# Power_Supply.net
KiCad netlist of a schematic drawn in Altium Designer
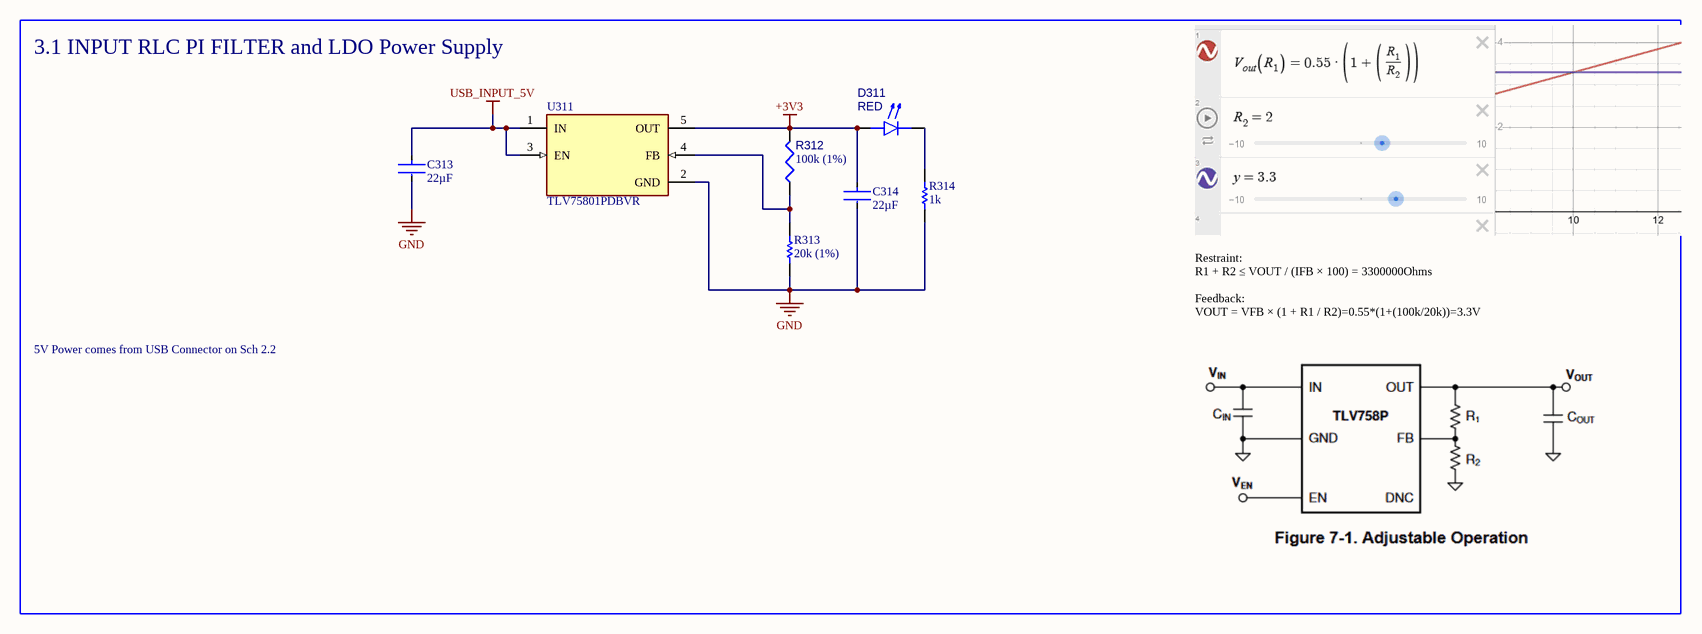
[diagram p0: Power Supply.SchDoc]

(export (version "E")
  (design (tool "Eeschema 10.0.6"))
  (components
    (comp (ref "C313")
      (value "22µF")
      (footprint "FP-GRM21B-0_2-e0_2_0_7-MFG")
      (fields (field (name "Comment") "GRM21BZ71A226ME15L"))
      (libsource (lib "University of British Columbia") (part "b4654b650e69147ec39a6b967a45e02"))
    )
    (comp (ref "C314")
      (value "22µF")
      (footprint "FP-GRM21B-0_2-e0_2_0_7-MFG")
      (fields (field (name "Comment") "GRM21BZ71A226ME15L"))
      (libsource (lib "University of British Columbia") (part "b4654b650e69147ec39a6b967a45e02"))
    )
    (comp (ref "D311")
      (value "RED")
      (footprint "WL-SMCW_0603_150060xx75000")
      (description "Single Color LED, Red, Water Clear, 1.1mm")
      (libsource (lib "University of British Columbia") (part "DIODE-LED-2"))
    )
    (comp (ref "R312")
      (value "100k (1%)")
      (footprint "RESC1608X55X25ML10T15")
      (description "Chip Resistor, 100 KOhm, +/- 1%, 0.1 W, -55 to 155 degC, 0603 (1608 Metric)")
      (fields (field (name "TOLERANCE") "1%") (field (name "POWER") "100mW"))
      (libsource (lib "University of British Columbia") (part "RES-2"))
    )
    (comp (ref "R313")
      (value "20k (1%)")
      (footprint "RESC1608X55X25ML10T15")
      (fields
        (field (name "POWER") "100mW")
        (field (name "TOLERANCE") "1%")
        (field (name "Comment") "RC0603FR-1320KL")
      )
      (libsource (lib "University of British Columbia") (part "RES"))
    )
    (comp (ref "R314")
      (value "1k")
      (footprint "RESC2013X60X35ML10T20")
      (fields
        (field (name "TOLERANCE") "1%")
        (field (name "POWER") "125mW")
        (field (name "Comment") "RC0805FR-071KL")
      )
      (libsource (lib "") (part "RES-2_1"))
    )
    (comp (ref "U311")
      (value "TLV75801PDBVR")
      (footprint "FP-DBV0005A-IPC_B")
      (description "Adjustable Positive LDO Regulator, 0.55V Min, 5.5V Max, PDSO5")
      (libsource (lib "University of British Columbia") (part "ed3a5c7a2f2d19c5e1dcfd7dcd5e996"))
    )
  )
  (nets
    (net (code "1") (name "+3V3") (class "Default")
      (node (ref "C314") (pin "1") (pinfunction "1_1") (pintype "passive"))
      (node (ref "D311") (pin "2") (pinfunction "A_2") (pintype "passive"))
      (node (ref "R312") (pin "2") (pinfunction "2_2") (pintype "passive"))
      (node (ref "U311") (pin "5") (pinfunction "OUT_5") (pintype "passive"))
    )
    (net (code "2") (name "GND") (class "Default")
      (node (ref "C313") (pin "2") (pinfunction "2_2") (pintype "passive"))
      (node (ref "C314") (pin "2") (pinfunction "2_2") (pintype "passive"))
      (node (ref "R313") (pin "2") (pinfunction "2_2") (pintype "passive"))
      (node (ref "R314") (pin "1") (pinfunction "1_1") (pintype "passive"))
      (node (ref "U311") (pin "2") (pinfunction "GND_2") (pintype "power_in"))
    )
    (net (code "3") (name "Net-(D311-K)") (class "Default")
      (node (ref "D311") (pin "1") (pinfunction "K_1") (pintype "passive"))
      (node (ref "R314") (pin "2") (pinfunction "2_2") (pintype "passive"))
    )
    (net (code "4") (name "Net-(U311-FB)") (class "Default")
      (node (ref "R312") (pin "1") (pinfunction "1_1") (pintype "passive"))
      (node (ref "R313") (pin "1") (pinfunction "1_1") (pintype "passive"))
      (node (ref "U311") (pin "4") (pinfunction "FB_4") (pintype "input"))
    )
    (net (code "5") (name "USB_INPUT_5V") (class "Default")
      (node (ref "C313") (pin "1") (pinfunction "1_1") (pintype "passive"))
      (node (ref "U311") (pin "1") (pinfunction "IN_1") (pintype "power_in"))
      (node (ref "U311") (pin "3") (pinfunction "EN_3") (pintype "input"))
    )
  )
)
